# EIB_A79024-001.net
KiCad netlist of a schematic drawn in EAGLE
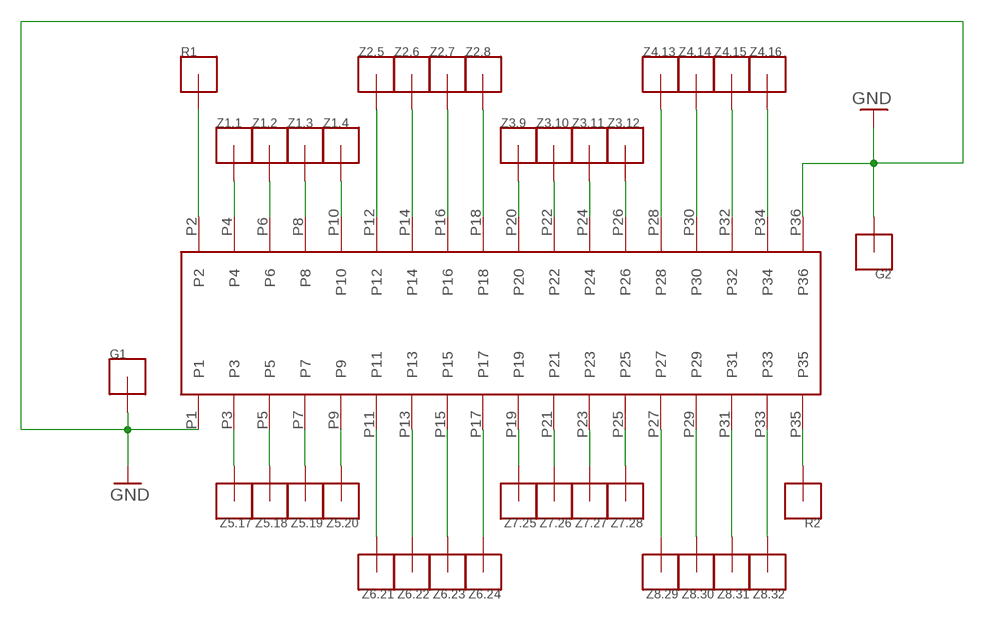
[diagram p0: schematic, sheet 1]

(export (version "E")
  (design (tool "Eeschema 10.0.6"))
  (components
    (comp (ref "A79024")
      (value "OMNETICS")
      (footprint "eagle-import:A79024")
      (libsource (lib "eagle-import") (part "OMNETICS"))
    )
    (comp (ref "G1")
      (value "S_P_HOLE")
      (footprint "eagle-import:S_P_HOLE")
      (libsource (lib "eagle-import") (part "S_P_HOLE"))
    )
    (comp (ref "G2")
      (value "S_P_HOLE")
      (footprint "eagle-import:S_P_HOLE")
      (libsource (lib "eagle-import") (part "S_P_HOLE"))
    )
    (comp (ref "R1")
      (value "S_P_HOLE")
      (footprint "eagle-import:S_P_HOLE")
      (libsource (lib "eagle-import") (part "S_P_HOLE"))
    )
    (comp (ref "R2")
      (value "S_P_HOLE")
      (footprint "eagle-import:S_P_HOLE")
      (libsource (lib "eagle-import") (part "S_P_HOLE"))
    )
    (comp (ref "Z1.1")
      (value "S_P_HOLE")
      (footprint "eagle-import:S_P_HOLE")
      (libsource (lib "eagle-import") (part "S_P_HOLE"))
    )
    (comp (ref "Z1.2")
      (value "S_P_HOLE")
      (footprint "eagle-import:S_P_HOLE")
      (libsource (lib "eagle-import") (part "S_P_HOLE"))
    )
    (comp (ref "Z1.3")
      (value "S_P_HOLE")
      (footprint "eagle-import:S_P_HOLE")
      (libsource (lib "eagle-import") (part "S_P_HOLE"))
    )
    (comp (ref "Z1.4")
      (value "S_P_HOLE")
      (footprint "eagle-import:S_P_HOLE")
      (libsource (lib "eagle-import") (part "S_P_HOLE"))
    )
    (comp (ref "Z2.5")
      (value "S_P_HOLE")
      (footprint "eagle-import:S_P_HOLE")
      (libsource (lib "eagle-import") (part "S_P_HOLE"))
    )
    (comp (ref "Z2.6")
      (value "S_P_HOLE")
      (footprint "eagle-import:S_P_HOLE")
      (libsource (lib "eagle-import") (part "S_P_HOLE"))
    )
    (comp (ref "Z2.7")
      (value "S_P_HOLE")
      (footprint "eagle-import:S_P_HOLE")
      (libsource (lib "eagle-import") (part "S_P_HOLE"))
    )
    (comp (ref "Z2.8")
      (value "S_P_HOLE")
      (footprint "eagle-import:S_P_HOLE")
      (libsource (lib "eagle-import") (part "S_P_HOLE"))
    )
    (comp (ref "Z3.9")
      (value "S_P_HOLE")
      (footprint "eagle-import:S_P_HOLE")
      (libsource (lib "eagle-import") (part "S_P_HOLE"))
    )
    (comp (ref "Z3.10")
      (value "S_P_HOLE")
      (footprint "eagle-import:S_P_HOLE")
      (libsource (lib "eagle-import") (part "S_P_HOLE"))
    )
    (comp (ref "Z3.11")
      (value "S_P_HOLE")
      (footprint "eagle-import:S_P_HOLE")
      (libsource (lib "eagle-import") (part "S_P_HOLE"))
    )
    (comp (ref "Z3.12")
      (value "S_P_HOLE")
      (footprint "eagle-import:S_P_HOLE")
      (libsource (lib "eagle-import") (part "S_P_HOLE"))
    )
    (comp (ref "Z4.13")
      (value "S_P_HOLE")
      (footprint "eagle-import:S_P_HOLE")
      (libsource (lib "eagle-import") (part "S_P_HOLE"))
    )
    (comp (ref "Z4.14")
      (value "S_P_HOLE")
      (footprint "eagle-import:S_P_HOLE")
      (libsource (lib "eagle-import") (part "S_P_HOLE"))
    )
    (comp (ref "Z4.15")
      (value "S_P_HOLE")
      (footprint "eagle-import:S_P_HOLE")
      (libsource (lib "eagle-import") (part "S_P_HOLE"))
    )
    (comp (ref "Z4.16")
      (value "S_P_HOLE")
      (footprint "eagle-import:S_P_HOLE")
      (libsource (lib "eagle-import") (part "S_P_HOLE"))
    )
    (comp (ref "Z5.17")
      (value "S_P_HOLE")
      (footprint "eagle-import:S_P_HOLE")
      (libsource (lib "eagle-import") (part "S_P_HOLE"))
    )
    (comp (ref "Z5.18")
      (value "S_P_HOLE")
      (footprint "eagle-import:S_P_HOLE")
      (libsource (lib "eagle-import") (part "S_P_HOLE"))
    )
    (comp (ref "Z5.19")
      (value "S_P_HOLE")
      (footprint "eagle-import:S_P_HOLE")
      (libsource (lib "eagle-import") (part "S_P_HOLE"))
    )
    (comp (ref "Z5.20")
      (value "S_P_HOLE")
      (footprint "eagle-import:S_P_HOLE")
      (libsource (lib "eagle-import") (part "S_P_HOLE"))
    )
    (comp (ref "Z6.21")
      (value "S_P_HOLE")
      (footprint "eagle-import:S_P_HOLE")
      (libsource (lib "eagle-import") (part "S_P_HOLE"))
    )
    (comp (ref "Z6.22")
      (value "S_P_HOLE")
      (footprint "eagle-import:S_P_HOLE")
      (libsource (lib "eagle-import") (part "S_P_HOLE"))
    )
    (comp (ref "Z6.23")
      (value "S_P_HOLE")
      (footprint "eagle-import:S_P_HOLE")
      (libsource (lib "eagle-import") (part "S_P_HOLE"))
    )
    (comp (ref "Z6.24")
      (value "S_P_HOLE")
      (footprint "eagle-import:S_P_HOLE")
      (libsource (lib "eagle-import") (part "S_P_HOLE"))
    )
    (comp (ref "Z7.25")
      (value "S_P_HOLE")
      (footprint "eagle-import:S_P_HOLE")
      (libsource (lib "eagle-import") (part "S_P_HOLE"))
    )
    (comp (ref "Z7.26")
      (value "S_P_HOLE")
      (footprint "eagle-import:S_P_HOLE")
      (libsource (lib "eagle-import") (part "S_P_HOLE"))
    )
    (comp (ref "Z7.27")
      (value "S_P_HOLE")
      (footprint "eagle-import:S_P_HOLE")
      (libsource (lib "eagle-import") (part "S_P_HOLE"))
    )
    (comp (ref "Z7.28")
      (value "S_P_HOLE")
      (footprint "eagle-import:S_P_HOLE")
      (libsource (lib "eagle-import") (part "S_P_HOLE"))
    )
    (comp (ref "Z8.29")
      (value "S_P_HOLE")
      (footprint "eagle-import:S_P_HOLE")
      (libsource (lib "eagle-import") (part "S_P_HOLE"))
    )
    (comp (ref "Z8.30")
      (value "S_P_HOLE")
      (footprint "eagle-import:S_P_HOLE")
      (libsource (lib "eagle-import") (part "S_P_HOLE"))
    )
    (comp (ref "Z8.31")
      (value "S_P_HOLE")
      (footprint "eagle-import:S_P_HOLE")
      (libsource (lib "eagle-import") (part "S_P_HOLE"))
    )
    (comp (ref "Z8.32")
      (value "S_P_HOLE")
      (footprint "eagle-import:S_P_HOLE")
      (libsource (lib "eagle-import") (part "S_P_HOLE"))
    )
  )
  (nets
    (net (code "1") (name "GND") (class "Default")
      (node (ref "A79024") (pin "P1") (pinfunction "P1_P1") (pintype "bidirectional"))
      (node (ref "A79024") (pin "P36") (pinfunction "P36_P36") (pintype "bidirectional"))
      (node (ref "G1") (pin "P1") (pinfunction "P1_P1") (pintype "bidirectional"))
      (node (ref "G2") (pin "P1") (pinfunction "P1_P1") (pintype "bidirectional"))
    )
    (net (code "2") (name "Net-(A79024-PadP2)") (class "Default")
      (node (ref "A79024") (pin "P2") (pinfunction "P2_P2") (pintype "bidirectional"))
      (node (ref "R1") (pin "P1") (pinfunction "P1_P1") (pintype "bidirectional"))
    )
    (net (code "3") (name "Net-(A79024-PadP3)") (class "Default")
      (node (ref "A79024") (pin "P3") (pinfunction "P3_P3") (pintype "bidirectional"))
      (node (ref "Z5.17") (pin "P1") (pinfunction "P1_P1") (pintype "bidirectional"))
    )
    (net (code "4") (name "Net-(A79024-PadP4)") (class "Default")
      (node (ref "A79024") (pin "P4") (pinfunction "P4_P4") (pintype "bidirectional"))
      (node (ref "Z1.1") (pin "P1") (pinfunction "P1_P1") (pintype "bidirectional"))
    )
    (net (code "5") (name "Net-(A79024-PadP5)") (class "Default")
      (node (ref "A79024") (pin "P5") (pinfunction "P5_P5") (pintype "bidirectional"))
      (node (ref "Z5.18") (pin "P1") (pinfunction "P1_P1") (pintype "bidirectional"))
    )
    (net (code "6") (name "Net-(A79024-PadP6)") (class "Default")
      (node (ref "A79024") (pin "P6") (pinfunction "P6_P6") (pintype "bidirectional"))
      (node (ref "Z1.2") (pin "P1") (pinfunction "P1_P1") (pintype "bidirectional"))
    )
    (net (code "7") (name "Net-(A79024-PadP7)") (class "Default")
      (node (ref "A79024") (pin "P7") (pinfunction "P7_P7") (pintype "bidirectional"))
      (node (ref "Z5.19") (pin "P1") (pinfunction "P1_P1") (pintype "bidirectional"))
    )
    (net (code "8") (name "Net-(A79024-PadP8)") (class "Default")
      (node (ref "A79024") (pin "P8") (pinfunction "P8_P8") (pintype "bidirectional"))
      (node (ref "Z1.3") (pin "P1") (pinfunction "P1_P1") (pintype "bidirectional"))
    )
    (net (code "9") (name "Net-(A79024-PadP9)") (class "Default")
      (node (ref "A79024") (pin "P9") (pinfunction "P9_P9") (pintype "bidirectional"))
      (node (ref "Z5.20") (pin "P1") (pinfunction "P1_P1") (pintype "bidirectional"))
    )
    (net (code "10") (name "Net-(A79024-PadP10)") (class "Default")
      (node (ref "A79024") (pin "P10") (pinfunction "P10_P10") (pintype "bidirectional"))
      (node (ref "Z1.4") (pin "P1") (pinfunction "P1_P1") (pintype "bidirectional"))
    )
    (net (code "11") (name "Net-(A79024-PadP11)") (class "Default")
      (node (ref "A79024") (pin "P11") (pinfunction "P11_P11") (pintype "bidirectional"))
      (node (ref "Z6.21") (pin "P1") (pinfunction "P1_P1") (pintype "bidirectional"))
    )
    (net (code "12") (name "Net-(A79024-PadP12)") (class "Default")
      (node (ref "A79024") (pin "P12") (pinfunction "P12_P12") (pintype "bidirectional"))
      (node (ref "Z2.5") (pin "P1") (pinfunction "P1_P1") (pintype "bidirectional"))
    )
    (net (code "13") (name "Net-(A79024-PadP13)") (class "Default")
      (node (ref "A79024") (pin "P13") (pinfunction "P13_P13") (pintype "bidirectional"))
      (node (ref "Z6.22") (pin "P1") (pinfunction "P1_P1") (pintype "bidirectional"))
    )
    (net (code "14") (name "Net-(A79024-PadP14)") (class "Default")
      (node (ref "A79024") (pin "P14") (pinfunction "P14_P14") (pintype "bidirectional"))
      (node (ref "Z2.6") (pin "P1") (pinfunction "P1_P1") (pintype "bidirectional"))
    )
    (net (code "15") (name "Net-(A79024-PadP15)") (class "Default")
      (node (ref "A79024") (pin "P15") (pinfunction "P15_P15") (pintype "bidirectional"))
      (node (ref "Z6.23") (pin "P1") (pinfunction "P1_P1") (pintype "bidirectional"))
    )
    (net (code "16") (name "Net-(A79024-PadP16)") (class "Default")
      (node (ref "A79024") (pin "P16") (pinfunction "P16_P16") (pintype "bidirectional"))
      (node (ref "Z2.7") (pin "P1") (pinfunction "P1_P1") (pintype "bidirectional"))
    )
    (net (code "17") (name "Net-(A79024-PadP17)") (class "Default")
      (node (ref "A79024") (pin "P17") (pinfunction "P17_P17") (pintype "bidirectional"))
      (node (ref "Z6.24") (pin "P1") (pinfunction "P1_P1") (pintype "bidirectional"))
    )
    (net (code "18") (name "Net-(A79024-PadP18)") (class "Default")
      (node (ref "A79024") (pin "P18") (pinfunction "P18_P18") (pintype "bidirectional"))
      (node (ref "Z2.8") (pin "P1") (pinfunction "P1_P1") (pintype "bidirectional"))
    )
    (net (code "19") (name "Net-(A79024-PadP19)") (class "Default")
      (node (ref "A79024") (pin "P19") (pinfunction "P19_P19") (pintype "bidirectional"))
      (node (ref "Z7.25") (pin "P1") (pinfunction "P1_P1") (pintype "bidirectional"))
    )
    (net (code "20") (name "Net-(A79024-PadP20)") (class "Default")
      (node (ref "A79024") (pin "P20") (pinfunction "P20_P20") (pintype "bidirectional"))
      (node (ref "Z3.9") (pin "P1") (pinfunction "P1_P1") (pintype "bidirectional"))
    )
    (net (code "21") (name "Net-(A79024-PadP21)") (class "Default")
      (node (ref "A79024") (pin "P21") (pinfunction "P21_P21") (pintype "bidirectional"))
      (node (ref "Z7.26") (pin "P1") (pinfunction "P1_P1") (pintype "bidirectional"))
    )
    (net (code "22") (name "Net-(A79024-PadP22)") (class "Default")
      (node (ref "A79024") (pin "P22") (pinfunction "P22_P22") (pintype "bidirectional"))
      (node (ref "Z3.10") (pin "P1") (pinfunction "P1_P1") (pintype "bidirectional"))
    )
    (net (code "23") (name "Net-(A79024-PadP23)") (class "Default")
      (node (ref "A79024") (pin "P23") (pinfunction "P23_P23") (pintype "bidirectional"))
      (node (ref "Z7.27") (pin "P1") (pinfunction "P1_P1") (pintype "bidirectional"))
    )
    (net (code "24") (name "Net-(A79024-PadP24)") (class "Default")
      (node (ref "A79024") (pin "P24") (pinfunction "P24_P24") (pintype "bidirectional"))
      (node (ref "Z3.11") (pin "P1") (pinfunction "P1_P1") (pintype "bidirectional"))
    )
    (net (code "25") (name "Net-(A79024-PadP25)") (class "Default")
      (node (ref "A79024") (pin "P25") (pinfunction "P25_P25") (pintype "bidirectional"))
      (node (ref "Z7.28") (pin "P1") (pinfunction "P1_P1") (pintype "bidirectional"))
    )
    (net (code "26") (name "Net-(A79024-PadP26)") (class "Default")
      (node (ref "A79024") (pin "P26") (pinfunction "P26_P26") (pintype "bidirectional"))
      (node (ref "Z3.12") (pin "P1") (pinfunction "P1_P1") (pintype "bidirectional"))
    )
    (net (code "27") (name "Net-(A79024-PadP27)") (class "Default")
      (node (ref "A79024") (pin "P27") (pinfunction "P27_P27") (pintype "bidirectional"))
      (node (ref "Z8.29") (pin "P1") (pinfunction "P1_P1") (pintype "bidirectional"))
    )
    (net (code "28") (name "Net-(A79024-PadP28)") (class "Default")
      (node (ref "A79024") (pin "P28") (pinfunction "P28_P28") (pintype "bidirectional"))
      (node (ref "Z4.13") (pin "P1") (pinfunction "P1_P1") (pintype "bidirectional"))
    )
    (net (code "29") (name "Net-(A79024-PadP29)") (class "Default")
      (node (ref "A79024") (pin "P29") (pinfunction "P29_P29") (pintype "bidirectional"))
      (node (ref "Z8.30") (pin "P1") (pinfunction "P1_P1") (pintype "bidirectional"))
    )
    (net (code "30") (name "Net-(A79024-PadP30)") (class "Default")
      (node (ref "A79024") (pin "P30") (pinfunction "P30_P30") (pintype "bidirectional"))
      (node (ref "Z4.14") (pin "P1") (pinfunction "P1_P1") (pintype "bidirectional"))
    )
    (net (code "31") (name "Net-(A79024-PadP31)") (class "Default")
      (node (ref "A79024") (pin "P31") (pinfunction "P31_P31") (pintype "bidirectional"))
      (node (ref "Z8.31") (pin "P1") (pinfunction "P1_P1") (pintype "bidirectional"))
    )
    (net (code "32") (name "Net-(A79024-PadP32)") (class "Default")
      (node (ref "A79024") (pin "P32") (pinfunction "P32_P32") (pintype "bidirectional"))
      (node (ref "Z4.15") (pin "P1") (pinfunction "P1_P1") (pintype "bidirectional"))
    )
    (net (code "33") (name "Net-(A79024-PadP33)") (class "Default")
      (node (ref "A79024") (pin "P33") (pinfunction "P33_P33") (pintype "bidirectional"))
      (node (ref "Z8.32") (pin "P1") (pinfunction "P1_P1") (pintype "bidirectional"))
    )
    (net (code "34") (name "Net-(A79024-PadP34)") (class "Default")
      (node (ref "A79024") (pin "P34") (pinfunction "P34_P34") (pintype "bidirectional"))
      (node (ref "Z4.16") (pin "P1") (pinfunction "P1_P1") (pintype "bidirectional"))
    )
    (net (code "35") (name "Net-(A79024-PadP35)") (class "Default")
      (node (ref "A79024") (pin "P35") (pinfunction "P35_P35") (pintype "bidirectional"))
      (node (ref "R2") (pin "P1") (pinfunction "P1_P1") (pintype "bidirectional"))
    )
  )
)
